# MCU.net
KiCad netlist of a schematic drawn in Altium Designer
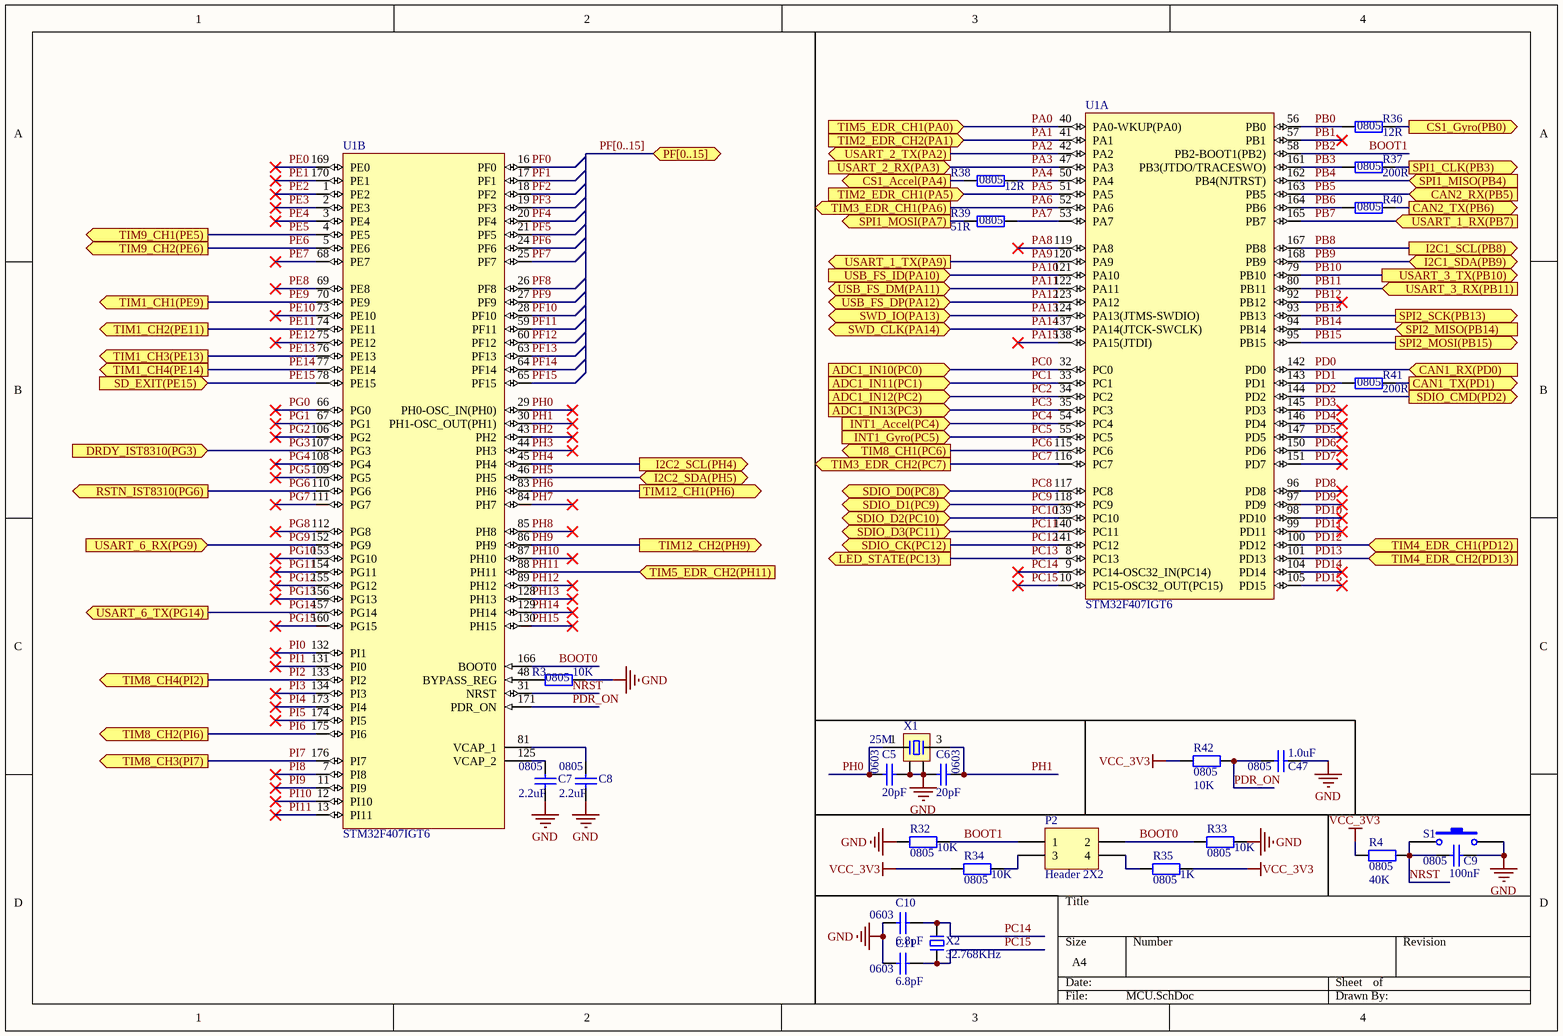
[diagram p0: MCU.SchDoc]

(export (version "E")
  (design (tool "Eeschema 10.0.6"))
  (components
    (comp (ref "C5")
      (value "0603")
      (footprint "C 0603_L")
      (fields (field (name "ALTIUM_VALUE") "20pF"))
      (libsource (lib "QT") (part "CAP"))
    )
    (comp (ref "C6")
      (value "0603")
      (footprint "C 0603_L")
      (fields (field (name "ALTIUM_VALUE") "20pF"))
      (libsource (lib "QT") (part "CAP"))
    )
    (comp (ref "C7")
      (value "0805")
      (footprint "C 0805_M")
      (fields (field (name "ALTIUM_VALUE") "2.2uF"))
      (libsource (lib "QT") (part "CAP"))
    )
    (comp (ref "C8")
      (value "0805")
      (footprint "C 0805_M")
      (fields (field (name "ALTIUM_VALUE") "2.2uF"))
      (libsource (lib "QT") (part "CAP"))
    )
    (comp (ref "C9")
      (value "0805")
      (footprint "C 0805_M")
      (fields (field (name "ALTIUM_VALUE") "100nF"))
      (libsource (lib "QT") (part "CAP"))
    )
    (comp (ref "C10")
      (value "0603")
      (footprint "C 0603_M")
      (fields (field (name "ALTIUM_VALUE") "6.8pF"))
      (libsource (lib "QT") (part "CAP"))
    )
    (comp (ref "C11")
      (value "0603")
      (footprint "C 0603_L")
      (fields (field (name "ALTIUM_VALUE") "6.8pF"))
      (libsource (lib "QT") (part "CAP"))
    )
    (comp (ref "C47")
      (value "0805")
      (footprint "C 0805_M")
      (fields (field (name "ALTIUM_VALUE") "1.0uF"))
      (libsource (lib "QT") (part "CAP"))
    )
    (comp (ref "P2")
      (value "Header 2X2")
      (footprint "HDR2.54-LI-2x2P")
      (description "Header, 2-Pin, Dual row")
      (fields (field (name "PUBLISHER") "Altium Limited"))
      (libsource (lib "QT") (part "Header 2X2"))
    )
    (comp (ref "R3")
      (value "0805")
      (footprint "R 0805_L")
      (description "Resistor")
      (fields (field (name "ALTIUM_VALUE") "10K") (field (name "PUBLISHER") "Altium Limited"))
      (libsource (lib "QT") (part "RES2"))
    )
    (comp (ref "R4")
      (value "0805")
      (footprint "R 0805_L")
      (description "Resistor")
      (fields (field (name "ALTIUM_VALUE") "40K") (field (name "PUBLISHER") "Altium Limited"))
      (libsource (lib "QT") (part "RES2"))
    )
    (comp (ref "R32")
      (value "0805")
      (footprint "R 0805_L")
      (description "Resistor")
      (fields (field (name "ALTIUM_VALUE") "10K") (field (name "PUBLISHER") "Altium Limited"))
      (libsource (lib "QT") (part "RES2"))
    )
    (comp (ref "R33")
      (value "0805")
      (footprint "R 0805_L")
      (description "Resistor")
      (fields (field (name "ALTIUM_VALUE") "10K") (field (name "PUBLISHER") "Altium Limited"))
      (libsource (lib "QT") (part "RES2"))
    )
    (comp (ref "R34")
      (value "0805")
      (footprint "R 0805_L")
      (description "Resistor")
      (fields (field (name "ALTIUM_VALUE") "10K") (field (name "PUBLISHER") "Altium Limited"))
      (libsource (lib "QT") (part "RES2"))
    )
    (comp (ref "R35")
      (value "0805")
      (footprint "R 0805_L")
      (description "Resistor")
      (fields (field (name "ALTIUM_VALUE") "1K") (field (name "PUBLISHER") "Altium Limited"))
      (libsource (lib "QT") (part "RES2"))
    )
    (comp (ref "R36")
      (value "0805")
      (footprint "R 0805_L")
      (description "Resistor")
      (fields (field (name "ALTIUM_VALUE") "12R") (field (name "PUBLISHER") "Altium Limited"))
      (libsource (lib "QT") (part "RES2"))
    )
    (comp (ref "R37")
      (value "0805")
      (footprint "R 0805_L")
      (description "Resistor")
      (fields (field (name "ALTIUM_VALUE") "200R") (field (name "PUBLISHER") "Altium Limited"))
      (libsource (lib "QT") (part "RES2"))
    )
    (comp (ref "R38")
      (value "0805")
      (footprint "R 0805_L")
      (description "Resistor")
      (fields (field (name "ALTIUM_VALUE") "12R") (field (name "PUBLISHER") "Altium Limited"))
      (libsource (lib "QT") (part "RES2"))
    )
    (comp (ref "R39")
      (value "0805")
      (footprint "R 0805_L")
      (description "Resistor")
      (fields (field (name "ALTIUM_VALUE") "51R") (field (name "PUBLISHER") "Altium Limited"))
      (libsource (lib "QT") (part "RES2"))
    )
    (comp (ref "R40")
      (value "0805")
      (footprint "R 0805_L")
      (description "Resistor")
      (fields (field (name "PUBLISHER") "Altium Limited"))
      (libsource (lib "QT") (part "RES2"))
    )
    (comp (ref "R41")
      (value "0805")
      (footprint "R 0805_L")
      (description "Resistor")
      (fields (field (name "ALTIUM_VALUE") "200R") (field (name "PUBLISHER") "Altium Limited"))
      (libsource (lib "QT") (part "RES2"))
    )
    (comp (ref "R42")
      (value "0805")
      (footprint "R 0805_L")
      (description "Resistor")
      (fields (field (name "ALTIUM_VALUE") "10K") (field (name "PUBLISHER") "Altium Limited"))
      (libsource (lib "QT") (part "RES2"))
    )
    (comp (ref "S1")
      (value "SW")
      (footprint "TSW DIP-3*6*4.3")
      (fields (field (name "PUBLISHER") "Altium Limited"))
      (libsource (lib "QT") (part "SW"))
    )
    (comp (ref "U1")
      (value "STM32F407IGT6")
      (footprint "STM-LQFP176_N")
      (fields (field (name "MANUFACTURER") "STMicroelectronics"))
      (libsource (lib "STMicroelectronics STM32 F4") (part "STM32F407IGT6"))
    )
    (comp (ref "X1")
      (value "25M")
      (footprint "XTAL-3225")
      (description "4脚晶振")
      (fields (field (name "版权归属") "源创客"))
      (libsource (lib "保险丝-晶振") (part "XTAL-4"))
    )
    (comp (ref "X2")
      (value "32.768KHz")
      (footprint "XTAL-3215A")
      (description "2脚晶振")
      (fields (field (name "版权归属") "源创客"))
      (libsource (lib "保险丝-晶振") (part "XTAL-2"))
    )
  )
  (nets
    (net (code "1") (name "/BOOT0") (class "Default")
      (node (ref "P2") (pin "2") (pinfunction "2_2") (pintype "passive"))
      (node (ref "R33") (pin "1") (pinfunction "1_1") (pintype "passive"))
      (node (ref "U1") (pin "166") (pinfunction "BOOT0_166") (pintype "input"))
    )
    (net (code "2") (name "/BOOT1") (class "Default")
      (node (ref "P2") (pin "1") (pinfunction "1_1") (pintype "passive"))
      (node (ref "R32") (pin "2") (pinfunction "2_2") (pintype "passive"))
      (node (ref "U1") (pin "58") (pinfunction "PB2-BOOT1(PB2)_58") (pintype "bidirectional"))
    )
    (net (code "3") (name "/CAN1_TX(PD1)") (class "Default")
      (node (ref "R41") (pin "2") (pinfunction "2_2") (pintype "passive"))
    )
    (net (code "4") (name "/CAN2_TX(PB6)") (class "Default")
      (node (ref "R40") (pin "2") (pinfunction "2_2") (pintype "passive"))
    )
    (net (code "5") (name "/CS1_Accel(PA4)") (class "Default")
      (node (ref "R38") (pin "1") (pinfunction "1_1") (pintype "passive"))
    )
    (net (code "6") (name "/CS1_Gyro(PB0)") (class "Default")
      (node (ref "R36") (pin "2") (pinfunction "2_2") (pintype "passive"))
    )
    (net (code "7") (name "/NRST") (class "Default")
      (node (ref "C9") (pin "2") (pinfunction "2_2") (pintype "passive"))
      (node (ref "R4") (pin "2") (pinfunction "2_2") (pintype "passive"))
      (node (ref "S1") (pin "1") (pinfunction "1_1") (pintype "passive"))
      (node (ref "U1") (pin "31") (pinfunction "NRST_31") (pintype "bidirectional"))
    )
    (net (code "8") (name "/PA0") (class "Default")
      (node (ref "U1") (pin "40") (pinfunction "PA0-WKUP(PA0)_40") (pintype "bidirectional"))
    )
    (net (code "9") (name "/PA1") (class "Default")
      (node (ref "U1") (pin "41") (pinfunction "PA1_41") (pintype "bidirectional"))
    )
    (net (code "10") (name "/PA2") (class "Default")
      (node (ref "U1") (pin "42") (pinfunction "PA2_42") (pintype "bidirectional"))
    )
    (net (code "11") (name "/PA3") (class "Default")
      (node (ref "U1") (pin "47") (pinfunction "PA3_47") (pintype "bidirectional"))
    )
    (net (code "12") (name "/PA4") (class "Default")
      (node (ref "R38") (pin "2") (pinfunction "2_2") (pintype "passive"))
      (node (ref "U1") (pin "50") (pinfunction "PA4_50") (pintype "bidirectional"))
    )
    (net (code "13") (name "/PA5") (class "Default")
      (node (ref "U1") (pin "51") (pinfunction "PA5_51") (pintype "bidirectional"))
    )
    (net (code "14") (name "/PA6") (class "Default")
      (node (ref "U1") (pin "52") (pinfunction "PA6_52") (pintype "bidirectional"))
    )
    (net (code "15") (name "/PA7") (class "Default")
      (node (ref "R39") (pin "2") (pinfunction "2_2") (pintype "passive"))
      (node (ref "U1") (pin "53") (pinfunction "PA7_53") (pintype "bidirectional"))
    )
    (net (code "16") (name "/PA8") (class "Default")
      (node (ref "U1") (pin "119") (pinfunction "PA8_119") (pintype "bidirectional+no_connect"))
    )
    (net (code "17") (name "/PA9") (class "Default")
      (node (ref "U1") (pin "120") (pinfunction "PA9_120") (pintype "bidirectional"))
    )
    (net (code "18") (name "/PA10") (class "Default")
      (node (ref "U1") (pin "121") (pinfunction "PA10_121") (pintype "bidirectional"))
    )
    (net (code "19") (name "/PA11") (class "Default")
      (node (ref "U1") (pin "122") (pinfunction "PA11_122") (pintype "bidirectional"))
    )
    (net (code "20") (name "/PA12") (class "Default")
      (node (ref "U1") (pin "123") (pinfunction "PA12_123") (pintype "bidirectional"))
    )
    (net (code "21") (name "/PA13") (class "Default")
      (node (ref "U1") (pin "124") (pinfunction "PA13(JTMS-SWDIO)_124") (pintype "bidirectional"))
    )
    (net (code "22") (name "/PA14") (class "Default")
      (node (ref "U1") (pin "137") (pinfunction "PA14(JTCK-SWCLK)_137") (pintype "bidirectional"))
    )
    (net (code "23") (name "/PA15") (class "Default")
      (node (ref "U1") (pin "138") (pinfunction "PA15(JTDI)_138") (pintype "bidirectional+no_connect"))
    )
    (net (code "24") (name "/PB0") (class "Default")
      (node (ref "R36") (pin "1") (pinfunction "1_1") (pintype "passive"))
      (node (ref "U1") (pin "56") (pinfunction "PB0_56") (pintype "bidirectional"))
    )
    (net (code "25") (name "/PB1") (class "Default")
      (node (ref "U1") (pin "57") (pinfunction "PB1_57") (pintype "bidirectional+no_connect"))
    )
    (net (code "26") (name "/PB3") (class "Default")
      (node (ref "R37") (pin "1") (pinfunction "1_1") (pintype "passive"))
      (node (ref "U1") (pin "161") (pinfunction "PB3(JTDO/TRACESWO)_161") (pintype "bidirectional"))
    )
    (net (code "27") (name "/PB4") (class "Default")
      (node (ref "U1") (pin "162") (pinfunction "PB4(NJTRST)_162") (pintype "bidirectional"))
    )
    (net (code "28") (name "/PB5") (class "Default")
      (node (ref "U1") (pin "163") (pinfunction "PB5_163") (pintype "bidirectional"))
    )
    (net (code "29") (name "/PB6") (class "Default")
      (node (ref "R40") (pin "1") (pinfunction "1_1") (pintype "passive"))
      (node (ref "U1") (pin "164") (pinfunction "PB6_164") (pintype "bidirectional"))
    )
    (net (code "30") (name "/PB7") (class "Default")
      (node (ref "U1") (pin "165") (pinfunction "PB7_165") (pintype "bidirectional"))
    )
    (net (code "31") (name "/PB8") (class "Default")
      (node (ref "U1") (pin "167") (pinfunction "PB8_167") (pintype "bidirectional"))
    )
    (net (code "32") (name "/PB9") (class "Default")
      (node (ref "U1") (pin "168") (pinfunction "PB9_168") (pintype "bidirectional"))
    )
    (net (code "33") (name "/PB10") (class "Default")
      (node (ref "U1") (pin "79") (pinfunction "PB10_79") (pintype "bidirectional"))
    )
    (net (code "34") (name "/PB11") (class "Default")
      (node (ref "U1") (pin "80") (pinfunction "PB11_80") (pintype "bidirectional"))
    )
    (net (code "35") (name "/PB12") (class "Default")
      (node (ref "U1") (pin "92") (pinfunction "PB12_92") (pintype "bidirectional+no_connect"))
    )
    (net (code "36") (name "/PB13") (class "Default")
      (node (ref "U1") (pin "93") (pinfunction "PB13_93") (pintype "bidirectional"))
    )
    (net (code "37") (name "/PB14") (class "Default")
      (node (ref "U1") (pin "94") (pinfunction "PB14_94") (pintype "bidirectional"))
    )
    (net (code "38") (name "/PB15") (class "Default")
      (node (ref "U1") (pin "95") (pinfunction "PB15_95") (pintype "bidirectional"))
    )
    (net (code "39") (name "/PC0") (class "Default")
      (node (ref "U1") (pin "32") (pinfunction "PC0_32") (pintype "bidirectional"))
    )
    (net (code "40") (name "/PC1") (class "Default")
      (node (ref "U1") (pin "33") (pinfunction "PC1_33") (pintype "bidirectional"))
    )
    (net (code "41") (name "/PC2") (class "Default")
      (node (ref "U1") (pin "34") (pinfunction "PC2_34") (pintype "bidirectional"))
    )
    (net (code "42") (name "/PC3") (class "Default")
      (node (ref "U1") (pin "35") (pinfunction "PC3_35") (pintype "bidirectional"))
    )
    (net (code "43") (name "/PC4") (class "Default")
      (node (ref "U1") (pin "54") (pinfunction "PC4_54") (pintype "bidirectional"))
    )
    (net (code "44") (name "/PC5") (class "Default")
      (node (ref "U1") (pin "55") (pinfunction "PC5_55") (pintype "bidirectional"))
    )
    (net (code "45") (name "/PC6") (class "Default")
      (node (ref "U1") (pin "115") (pinfunction "PC6_115") (pintype "bidirectional"))
    )
    (net (code "46") (name "/PC7") (class "Default")
      (node (ref "U1") (pin "116") (pinfunction "PC7_116") (pintype "bidirectional"))
    )
    (net (code "47") (name "/PC8") (class "Default")
      (node (ref "U1") (pin "117") (pinfunction "PC8_117") (pintype "bidirectional"))
    )
    (net (code "48") (name "/PC9") (class "Default")
      (node (ref "U1") (pin "118") (pinfunction "PC9_118") (pintype "bidirectional"))
    )
    (net (code "49") (name "/PC10") (class "Default")
      (node (ref "U1") (pin "139") (pinfunction "PC10_139") (pintype "bidirectional"))
    )
    (net (code "50") (name "/PC11") (class "Default")
      (node (ref "U1") (pin "140") (pinfunction "PC11_140") (pintype "bidirectional"))
    )
    (net (code "51") (name "/PC12") (class "Default")
      (node (ref "U1") (pin "141") (pinfunction "PC12_141") (pintype "bidirectional"))
    )
    (net (code "52") (name "/PC13") (class "Default")
      (node (ref "U1") (pin "8") (pinfunction "PC13_8") (pintype "bidirectional"))
    )
    (net (code "53") (name "/PC14") (class "Default")
      (node (ref "C10") (pin "2") (pinfunction "2_2") (pintype "passive"))
      (node (ref "U1") (pin "9") (pinfunction "PC14-OSC32_IN(PC14)_9") (pintype "bidirectional"))
      (node (ref "X2") (pin "2") (pinfunction "2_2") (pintype "passive"))
    )
    (net (code "54") (name "/PC15") (class "Default")
      (node (ref "C11") (pin "2") (pinfunction "2_2") (pintype "passive"))
      (node (ref "U1") (pin "10") (pinfunction "PC15-OSC32_OUT(PC15)_10") (pintype "bidirectional"))
      (node (ref "X2") (pin "1") (pinfunction "1_1") (pintype "passive"))
    )
    (net (code "55") (name "/PD0") (class "Default")
      (node (ref "U1") (pin "142") (pinfunction "PD0_142") (pintype "bidirectional"))
    )
    (net (code "56") (name "/PD1") (class "Default")
      (node (ref "R41") (pin "1") (pinfunction "1_1") (pintype "passive"))
      (node (ref "U1") (pin "143") (pinfunction "PD1_143") (pintype "bidirectional"))
    )
    (net (code "57") (name "/PD2") (class "Default")
      (node (ref "U1") (pin "144") (pinfunction "PD2_144") (pintype "bidirectional"))
    )
    (net (code "58") (name "/PD3") (class "Default")
      (node (ref "U1") (pin "145") (pinfunction "PD3_145") (pintype "bidirectional+no_connect"))
    )
    (net (code "59") (name "/PD4") (class "Default")
      (node (ref "U1") (pin "146") (pinfunction "PD4_146") (pintype "bidirectional+no_connect"))
    )
    (net (code "60") (name "/PD5") (class "Default")
      (node (ref "U1") (pin "147") (pinfunction "PD5_147") (pintype "bidirectional+no_connect"))
    )
    (net (code "61") (name "/PD6") (class "Default")
      (node (ref "U1") (pin "150") (pinfunction "PD6_150") (pintype "bidirectional+no_connect"))
    )
    (net (code "62") (name "/PD7") (class "Default")
      (node (ref "U1") (pin "151") (pinfunction "PD7_151") (pintype "bidirectional+no_connect"))
    )
    (net (code "63") (name "/PD8") (class "Default")
      (node (ref "U1") (pin "96") (pinfunction "PD8_96") (pintype "bidirectional+no_connect"))
    )
    (net (code "64") (name "/PD9") (class "Default")
      (node (ref "U1") (pin "97") (pinfunction "PD9_97") (pintype "bidirectional+no_connect"))
    )
    (net (code "65") (name "/PD10") (class "Default")
      (node (ref "U1") (pin "98") (pinfunction "PD10_98") (pintype "bidirectional+no_connect"))
    )
    (net (code "66") (name "/PD11") (class "Default")
      (node (ref "U1") (pin "99") (pinfunction "PD11_99") (pintype "bidirectional+no_connect"))
    )
    (net (code "67") (name "/PD12") (class "Default")
      (node (ref "U1") (pin "100") (pinfunction "PD12_100") (pintype "bidirectional"))
    )
    (net (code "68") (name "/PD13") (class "Default")
      (node (ref "U1") (pin "101") (pinfunction "PD13_101") (pintype "bidirectional"))
    )
    (net (code "69") (name "/PD14") (class "Default")
      (node (ref "U1") (pin "104") (pinfunction "PD14_104") (pintype "bidirectional+no_connect"))
    )
    (net (code "70") (name "/PD15") (class "Default")
      (node (ref "U1") (pin "105") (pinfunction "PD15_105") (pintype "bidirectional+no_connect"))
    )
    (net (code "71") (name "/PDR_ON") (class "Default")
      (node (ref "C47") (pin "2") (pinfunction "2_2") (pintype "passive"))
      (node (ref "R42") (pin "2") (pinfunction "2_2") (pintype "passive"))
      (node (ref "U1") (pin "171") (pinfunction "PDR_ON_171") (pintype "input"))
    )
    (net (code "72") (name "/PE0") (class "Default")
      (node (ref "U1") (pin "169") (pinfunction "PE0_169") (pintype "bidirectional+no_connect"))
    )
    (net (code "73") (name "/PE1") (class "Default")
      (node (ref "U1") (pin "170") (pinfunction "PE1_170") (pintype "bidirectional+no_connect"))
    )
    (net (code "74") (name "/PE2") (class "Default")
      (node (ref "U1") (pin "1") (pinfunction "PE2_1") (pintype "bidirectional+no_connect"))
    )
    (net (code "75") (name "/PE3") (class "Default")
      (node (ref "U1") (pin "2") (pinfunction "PE3_2") (pintype "bidirectional+no_connect"))
    )
    (net (code "76") (name "/PE4") (class "Default")
      (node (ref "U1") (pin "3") (pinfunction "PE4_3") (pintype "bidirectional+no_connect"))
    )
    (net (code "77") (name "/PE5") (class "Default")
      (node (ref "U1") (pin "4") (pinfunction "PE5_4") (pintype "bidirectional"))
    )
    (net (code "78") (name "/PE6") (class "Default")
      (node (ref "U1") (pin "5") (pinfunction "PE6_5") (pintype "bidirectional"))
    )
    (net (code "79") (name "/PE7") (class "Default")
      (node (ref "U1") (pin "68") (pinfunction "PE7_68") (pintype "bidirectional+no_connect"))
    )
    (net (code "80") (name "/PE8") (class "Default")
      (node (ref "U1") (pin "69") (pinfunction "PE8_69") (pintype "bidirectional+no_connect"))
    )
    (net (code "81") (name "/PE9") (class "Default")
      (node (ref "U1") (pin "70") (pinfunction "PE9_70") (pintype "bidirectional"))
    )
    (net (code "82") (name "/PE10") (class "Default")
      (node (ref "U1") (pin "73") (pinfunction "PE10_73") (pintype "bidirectional+no_connect"))
    )
    (net (code "83") (name "/PE11") (class "Default")
      (node (ref "U1") (pin "74") (pinfunction "PE11_74") (pintype "bidirectional"))
    )
    (net (code "84") (name "/PE12") (class "Default")
      (node (ref "U1") (pin "75") (pinfunction "PE12_75") (pintype "bidirectional+no_connect"))
    )
    (net (code "85") (name "/PE13") (class "Default")
      (node (ref "U1") (pin "76") (pinfunction "PE13_76") (pintype "bidirectional"))
    )
    (net (code "86") (name "/PE14") (class "Default")
      (node (ref "U1") (pin "77") (pinfunction "PE14_77") (pintype "bidirectional"))
    )
    (net (code "87") (name "/PE15") (class "Default")
      (node (ref "U1") (pin "78") (pinfunction "PE15_78") (pintype "bidirectional"))
    )
    (net (code "88") (name "/PF0") (class "Default")
      (node (ref "U1") (pin "16") (pinfunction "PF0_16") (pintype "bidirectional"))
    )
    (net (code "89") (name "/PF1") (class "Default")
      (node (ref "U1") (pin "17") (pinfunction "PF1_17") (pintype "bidirectional"))
    )
    (net (code "90") (name "/PF2") (class "Default")
      (node (ref "U1") (pin "18") (pinfunction "PF2_18") (pintype "bidirectional"))
    )
    (net (code "91") (name "/PF3") (class "Default")
      (node (ref "U1") (pin "19") (pinfunction "PF3_19") (pintype "bidirectional"))
    )
    (net (code "92") (name "/PF4") (class "Default")
      (node (ref "U1") (pin "20") (pinfunction "PF4_20") (pintype "bidirectional"))
    )
    (net (code "93") (name "/PF5") (class "Default")
      (node (ref "U1") (pin "21") (pinfunction "PF5_21") (pintype "bidirectional"))
    )
    (net (code "94") (name "/PF6") (class "Default")
      (node (ref "U1") (pin "24") (pinfunction "PF6_24") (pintype "bidirectional"))
    )
    (net (code "95") (name "/PF7") (class "Default")
      (node (ref "U1") (pin "25") (pinfunction "PF7_25") (pintype "bidirectional"))
    )
    (net (code "96") (name "/PF8") (class "Default")
      (node (ref "U1") (pin "26") (pinfunction "PF8_26") (pintype "bidirectional"))
    )
    (net (code "97") (name "/PF9") (class "Default")
      (node (ref "U1") (pin "27") (pinfunction "PF9_27") (pintype "bidirectional"))
    )
    (net (code "98") (name "/PF10") (class "Default")
      (node (ref "U1") (pin "28") (pinfunction "PF10_28") (pintype "bidirectional"))
    )
    (net (code "99") (name "/PF11") (class "Default")
      (node (ref "U1") (pin "59") (pinfunction "PF11_59") (pintype "bidirectional"))
    )
    (net (code "100") (name "/PF12") (class "Default")
      (node (ref "U1") (pin "60") (pinfunction "PF12_60") (pintype "bidirectional"))
    )
    (net (code "101") (name "/PF13") (class "Default")
      (node (ref "U1") (pin "63") (pinfunction "PF13_63") (pintype "bidirectional"))
    )
    (net (code "102") (name "/PF14") (class "Default")
      (node (ref "U1") (pin "64") (pinfunction "PF14_64") (pintype "bidirectional"))
    )
    (net (code "103") (name "/PF15") (class "Default")
      (node (ref "U1") (pin "65") (pinfunction "PF15_65") (pintype "bidirectional"))
    )
    (net (code "105") (name "/PG0") (class "Default")
      (node (ref "U1") (pin "66") (pinfunction "PG0_66") (pintype "bidirectional+no_connect"))
    )
    (net (code "106") (name "/PG1") (class "Default")
      (node (ref "U1") (pin "67") (pinfunction "PG1_67") (pintype "bidirectional+no_connect"))
    )
    (net (code "107") (name "/PG2") (class "Default")
      (node (ref "U1") (pin "106") (pinfunction "PG2_106") (pintype "bidirectional+no_connect"))
    )
    (net (code "108") (name "/PG3") (class "Default")
      (node (ref "U1") (pin "107") (pinfunction "PG3_107") (pintype "bidirectional"))
    )
    (net (code "109") (name "/PG4") (class "Default")
      (node (ref "U1") (pin "108") (pinfunction "PG4_108") (pintype "bidirectional+no_connect"))
    )
    (net (code "110") (name "/PG5") (class "Default")
      (node (ref "U1") (pin "109") (pinfunction "PG5_109") (pintype "bidirectional+no_connect"))
    )
    (net (code "111") (name "/PG6") (class "Default")
      (node (ref "U1") (pin "110") (pinfunction "PG6_110") (pintype "bidirectional"))
    )
    (net (code "112") (name "/PG7") (class "Default")
      (node (ref "U1") (pin "111") (pinfunction "PG7_111") (pintype "bidirectional+no_connect"))
    )
    (net (code "113") (name "/PG8") (class "Default")
      (node (ref "U1") (pin "112") (pinfunction "PG8_112") (pintype "bidirectional+no_connect"))
    )
    (net (code "114") (name "/PG9") (class "Default")
      (node (ref "U1") (pin "152") (pinfunction "PG9_152") (pintype "bidirectional"))
    )
    (net (code "115") (name "/PG10") (class "Default")
      (node (ref "U1") (pin "153") (pinfunction "PG10_153") (pintype "bidirectional+no_connect"))
    )
    (net (code "116") (name "/PG11") (class "Default")
      (node (ref "U1") (pin "154") (pinfunction "PG11_154") (pintype "bidirectional+no_connect"))
    )
    (net (code "117") (name "/PG12") (class "Default")
      (node (ref "U1") (pin "155") (pinfunction "PG12_155") (pintype "bidirectional+no_connect"))
    )
    (net (code "118") (name "/PG13") (class "Default")
      (node (ref "U1") (pin "156") (pinfunction "PG13_156") (pintype "bidirectional+no_connect"))
    )
    (net (code "119") (name "/PG14") (class "Default")
      (node (ref "U1") (pin "157") (pinfunction "PG14_157") (pintype "bidirectional"))
    )
    (net (code "120") (name "/PG15") (class "Default")
      (node (ref "U1") (pin "160") (pinfunction "PG15_160") (pintype "bidirectional+no_connect"))
    )
    (net (code "121") (name "/PH0") (class "Default")
      (node (ref "C5") (pin "1") (pinfunction "1_1") (pintype "passive"))
      (node (ref "U1") (pin "29") (pinfunction "PH0-OSC_IN(PH0)_29") (pintype "bidirectional"))
      (node (ref "X1") (pin "1") (pinfunction "1_1") (pintype "passive"))
    )
    (net (code "122") (name "/PH1") (class "Default")
      (node (ref "C6") (pin "2") (pinfunction "2_2") (pintype "passive"))
      (node (ref "U1") (pin "30") (pinfunction "PH1-OSC_OUT(PH1)_30") (pintype "bidirectional"))
      (node (ref "X1") (pin "3") (pinfunction "3_3") (pintype "passive"))
    )
    (net (code "123") (name "/PH2") (class "Default")
      (node (ref "U1") (pin "43") (pinfunction "PH2_43") (pintype "bidirectional+no_connect"))
    )
    (net (code "124") (name "/PH3") (class "Default")
      (node (ref "U1") (pin "44") (pinfunction "PH3_44") (pintype "bidirectional+no_connect"))
    )
    (net (code "125") (name "/PH4") (class "Default")
      (node (ref "U1") (pin "45") (pinfunction "PH4_45") (pintype "bidirectional"))
    )
    (net (code "126") (name "/PH5") (class "Default")
      (node (ref "U1") (pin "46") (pinfunction "PH5_46") (pintype "bidirectional"))
    )
    (net (code "127") (name "/PH6") (class "Default")
      (node (ref "U1") (pin "83") (pinfunction "PH6_83") (pintype "bidirectional"))
    )
    (net (code "128") (name "/PH7") (class "Default")
      (node (ref "U1") (pin "84") (pinfunction "PH7_84") (pintype "bidirectional+no_connect"))
    )
    (net (code "129") (name "/PH8") (class "Default")
      (node (ref "U1") (pin "85") (pinfunction "PH8_85") (pintype "bidirectional+no_connect"))
    )
    (net (code "130") (name "/PH9") (class "Default")
      (node (ref "U1") (pin "86") (pinfunction "PH9_86") (pintype "bidirectional"))
    )
    (net (code "131") (name "/PH10") (class "Default")
      (node (ref "U1") (pin "87") (pinfunction "PH10_87") (pintype "bidirectional+no_connect"))
    )
    (net (code "132") (name "/PH11") (class "Default")
      (node (ref "U1") (pin "88") (pinfunction "PH11_88") (pintype "bidirectional"))
    )
    (net (code "133") (name "/PH12") (class "Default")
      (node (ref "U1") (pin "89") (pinfunction "PH12_89") (pintype "bidirectional+no_connect"))
    )
    (net (code "134") (name "/PH13") (class "Default")
      (node (ref "U1") (pin "128") (pinfunction "PH13_128") (pintype "bidirectional+no_connect"))
    )
    (net (code "135") (name "/PH14") (class "Default")
      (node (ref "U1") (pin "129") (pinfunction "PH14_129") (pintype "bidirectional+no_connect"))
    )
    (net (code "136") (name "/PH15") (class "Default")
      (node (ref "U1") (pin "130") (pinfunction "PH15_130") (pintype "bidirectional+no_connect"))
    )
    (net (code "137") (name "/PI0") (class "Default")
      (node (ref "U1") (pin "132") (pinfunction "PI1_132") (pintype "bidirectional+no_connect"))
    )
    (net (code "138") (name "/PI1") (class "Default")
      (node (ref "U1") (pin "131") (pinfunction "PI0_131") (pintype "bidirectional+no_connect"))
    )
    (net (code "139") (name "/PI2") (class "Default")
      (node (ref "U1") (pin "133") (pinfunction "PI2_133") (pintype "bidirectional"))
    )
    (net (code "140") (name "/PI3") (class "Default")
      (node (ref "U1") (pin "134") (pinfunction "PI3_134") (pintype "bidirectional+no_connect"))
    )
    (net (code "141") (name "/PI4") (class "Default")
      (node (ref "U1") (pin "173") (pinfunction "PI4_173") (pintype "bidirectional+no_connect"))
    )
    (net (code "142") (name "/PI5") (class "Default")
      (node (ref "U1") (pin "174") (pinfunction "PI5_174") (pintype "bidirectional+no_connect"))
    )
    (net (code "143") (name "/PI6") (class "Default")
      (node (ref "U1") (pin "175") (pinfunction "PI6_175") (pintype "bidirectional"))
    )
    (net (code "144") (name "/PI7") (class "Default")
      (node (ref "U1") (pin "176") (pinfunction "PI7_176") (pintype "bidirectional"))
    )
    (net (code "145") (name "/PI8") (class "Default")
      (node (ref "U1") (pin "7") (pinfunction "PI8_7") (pintype "bidirectional+no_connect"))
    )
    (net (code "146") (name "/PI9") (class "Default")
      (node (ref "U1") (pin "11") (pinfunction "PI9_11") (pintype "bidirectional+no_connect"))
    )
    (net (code "147") (name "/PI10") (class "Default")
      (node (ref "U1") (pin "12") (pinfunction "PI10_12") (pintype "bidirectional+no_connect"))
    )
    (net (code "148") (name "/PI11") (class "Default")
      (node (ref "U1") (pin "13") (pinfunction "PI11_13") (pintype "bidirectional+no_connect"))
    )
    (net (code "149") (name "/SPI1_CLK(PB3)") (class "Default")
      (node (ref "R37") (pin "2") (pinfunction "2_2") (pintype "passive"))
    )
    (net (code "150") (name "/SPI1_MOSI(PA7)") (class "Default")
      (node (ref "R39") (pin "1") (pinfunction "1_1") (pintype "passive"))
    )
    (net (code "151") (name "GND") (class "Default")
      (node (ref "C10") (pin "1") (pinfunction "1_1") (pintype "passive"))
      (node (ref "C11") (pin "1") (pinfunction "1_1") (pintype "passive"))
      (node (ref "C47") (pin "1") (pinfunction "1_1") (pintype "passive"))
      (node (ref "C5") (pin "2") (pinfunction "2_2") (pintype "passive"))
      (node (ref "C6") (pin "1") (pinfunction "1_1") (pintype "passive"))
      (node (ref "C7") (pin "1") (pinfunction "1_1") (pintype "passive"))
      (node (ref "C8") (pin "1") (pinfunction "1_1") (pintype "passive"))
      (node (ref "C9") (pin "1") (pinfunction "1_1") (pintype "passive"))
      (node (ref "R3") (pin "2") (pinfunction "2_2") (pintype "passive"))
      (node (ref "R32") (pin "1") (pinfunction "1_1") (pintype "passive"))
      (node (ref "R33") (pin "2") (pinfunction "2_2") (pintype "passive"))
      (node (ref "S1") (pin "2") (pinfunction "2_2") (pintype "passive"))
      (node (ref "X1") (pin "2") (pinfunction "2_2") (pintype "passive"))
      (node (ref "X1") (pin "4") (pinfunction "4_4") (pintype "passive"))
    )
    (net (code "152") (name "Net-(P2-Pad3)") (class "Default")
      (node (ref "P2") (pin "3") (pinfunction "3_3") (pintype "passive"))
      (node (ref "R34") (pin "2") (pinfunction "2_2") (pintype "passive"))
    )
    (net (code "153") (name "Net-(P2-Pad4)") (class "Default")
      (node (ref "P2") (pin "4") (pinfunction "4_4") (pintype "passive"))
      (node (ref "R35") (pin "1") (pinfunction "1_1") (pintype "passive"))
    )
    (net (code "154") (name "Net-(U1B-BYPASS_REG)") (class "Default")
      (node (ref "R3") (pin "1") (pinfunction "1_1") (pintype "passive"))
      (node (ref "U1") (pin "48") (pinfunction "BYPASS_REG_48") (pintype "input"))
    )
    (net (code "155") (name "Net-(U1B-VCAP_1)") (class "Default")
      (node (ref "C8") (pin "2") (pinfunction "2_2") (pintype "passive"))
      (node (ref "U1") (pin "81") (pinfunction "VCAP_1_81") (pintype "power_in"))
    )
    (net (code "156") (name "Net-(U1B-VCAP_2)") (class "Default")
      (node (ref "C7") (pin "2") (pinfunction "2_2") (pintype "passive"))
      (node (ref "U1") (pin "125") (pinfunction "VCAP_2_125") (pintype "power_in"))
    )
    (net (code "157") (name "VCC_3V3") (class "Default")
      (node (ref "R34") (pin "1") (pinfunction "1_1") (pintype "passive"))
      (node (ref "R35") (pin "2") (pinfunction "2_2") (pintype "passive"))
      (node (ref "R4") (pin "1") (pinfunction "1_1") (pintype "passive"))
      (node (ref "R42") (pin "1") (pinfunction "1_1") (pintype "passive"))
    )
  )
)
